# BV100011_ControlDI_8-15.net
KiCad netlist of a schematic drawn in Altium Designer
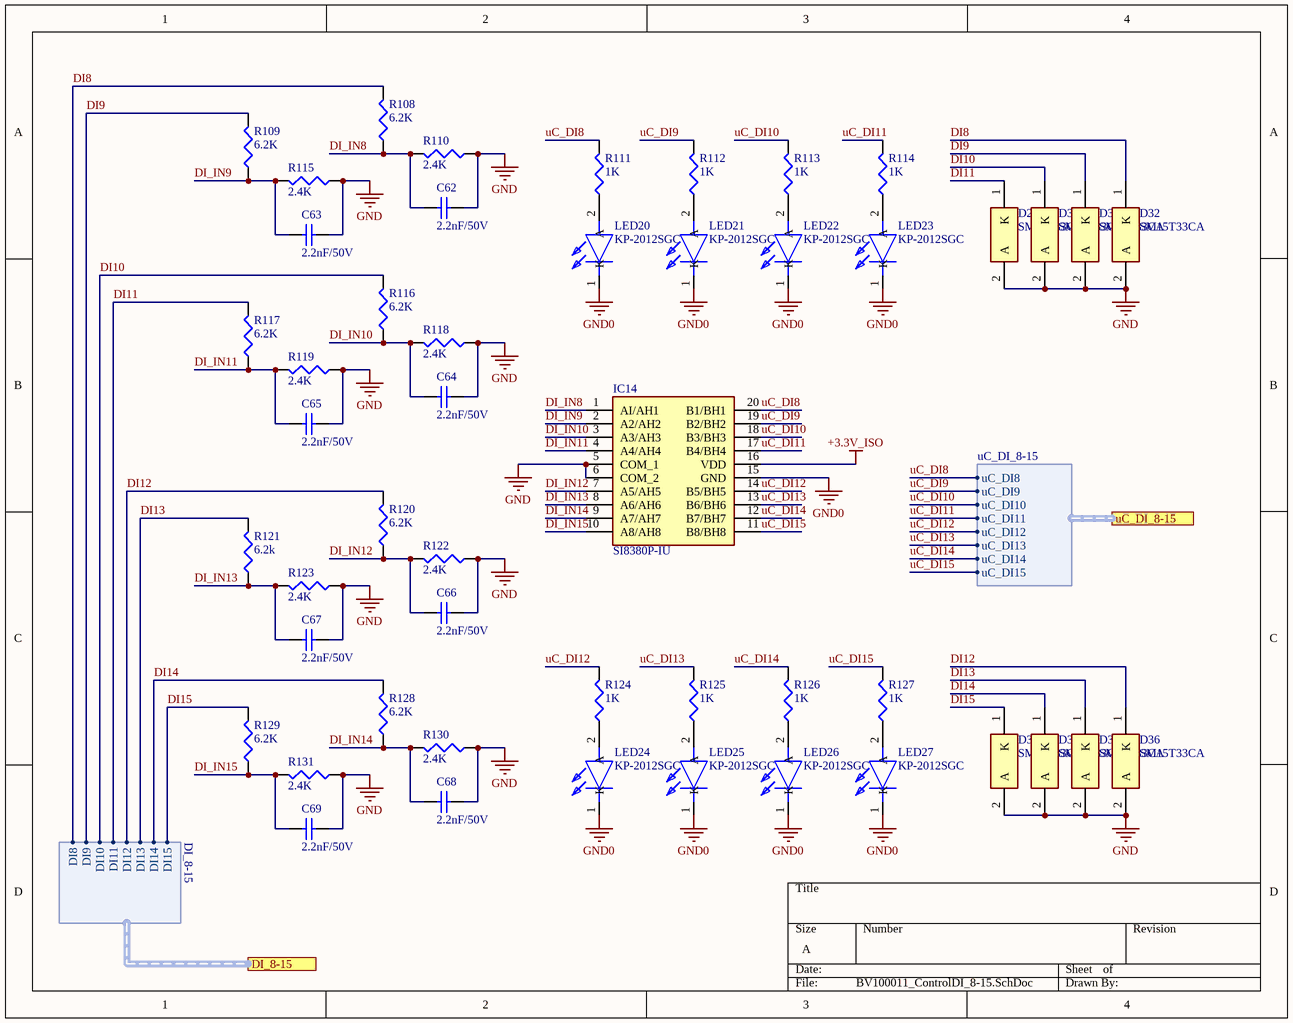
[diagram p0: BV100011_ControlDI_8-15.SchDoc]

(export (version "E")
  (design (tool "Eeschema 10.0.6"))
  (components
    (comp (ref "C62")
      (value "2.2nF/50V")
      (footprint "C1210")
      (description "Capacitor (Semiconductor SIM Model)")
      (fields (field (name "PUBLISHER") "Altium Limited"))
      (libsource (lib "Miscellaneous Devices") (part "Cap Semi"))
    )
    (comp (ref "C63")
      (value "2.2nF/50V")
      (footprint "C1210")
      (description "Capacitor (Semiconductor SIM Model)")
      (fields (field (name "PUBLISHER") "Altium Limited"))
      (libsource (lib "Miscellaneous Devices") (part "Cap Semi"))
    )
    (comp (ref "C64")
      (value "2.2nF/50V")
      (footprint "C1210")
      (description "Capacitor (Semiconductor SIM Model)")
      (fields (field (name "PUBLISHER") "Altium Limited"))
      (libsource (lib "Miscellaneous Devices") (part "Cap Semi"))
    )
    (comp (ref "C65")
      (value "2.2nF/50V")
      (footprint "C1210")
      (description "Capacitor (Semiconductor SIM Model)")
      (fields (field (name "PUBLISHER") "Altium Limited"))
      (libsource (lib "Miscellaneous Devices") (part "Cap Semi"))
    )
    (comp (ref "C66")
      (value "2.2nF/50V")
      (footprint "C1210")
      (description "Capacitor (Semiconductor SIM Model)")
      (fields (field (name "PUBLISHER") "Altium Limited"))
      (libsource (lib "Miscellaneous Devices") (part "Cap Semi"))
    )
    (comp (ref "C67")
      (value "2.2nF/50V")
      (footprint "C1210")
      (description "Capacitor (Semiconductor SIM Model)")
      (fields (field (name "PUBLISHER") "Altium Limited"))
      (libsource (lib "Miscellaneous Devices") (part "Cap Semi"))
    )
    (comp (ref "C68")
      (value "2.2nF/50V")
      (footprint "C1210")
      (description "Capacitor (Semiconductor SIM Model)")
      (fields (field (name "PUBLISHER") "Altium Limited"))
      (libsource (lib "Miscellaneous Devices") (part "Cap Semi"))
    )
    (comp (ref "C69")
      (value "2.2nF/50V")
      (footprint "C1210")
      (description "Capacitor (Semiconductor SIM Model)")
      (fields (field (name "PUBLISHER") "Altium Limited"))
      (libsource (lib "Miscellaneous Devices") (part "Cap Semi"))
    )
    (comp (ref "D29")
      (value "SM15T33CA")
      (footprint "DIONM8059X265N")
      (description "Diode")
      (fields (field (name "MOUSER PART NUMBER") "511-SM15T33CA") (field (name "RS PART NUMBER") "9196428"))
      (libsource (lib "SM15T33CA") (part "SM15T33CA"))
    )
    (comp (ref "D30")
      (value "SM15T33CA")
      (footprint "DIONM8059X265N")
      (description "Diode")
      (fields (field (name "MOUSER PART NUMBER") "511-SM15T33CA") (field (name "RS PART NUMBER") "9196428"))
      (libsource (lib "SM15T33CA") (part "SM15T33CA"))
    )
    (comp (ref "D31")
      (value "SM15T33CA")
      (footprint "DIONM8059X265N")
      (description "Diode")
      (fields (field (name "MOUSER PART NUMBER") "511-SM15T33CA") (field (name "RS PART NUMBER") "9196428"))
      (libsource (lib "SM15T33CA") (part "SM15T33CA"))
    )
    (comp (ref "D32")
      (value "SM15T33CA")
      (footprint "DIONM8059X265N")
      (description "Diode")
      (fields (field (name "MOUSER PART NUMBER") "511-SM15T33CA") (field (name "RS PART NUMBER") "9196428"))
      (libsource (lib "SM15T33CA") (part "SM15T33CA"))
    )
    (comp (ref "D33")
      (value "SM15T33CA")
      (footprint "DIONM8059X265N")
      (description "Diode")
      (fields (field (name "MOUSER PART NUMBER") "511-SM15T33CA") (field (name "RS PART NUMBER") "9196428"))
      (libsource (lib "SM15T33CA") (part "SM15T33CA"))
    )
    (comp (ref "D34")
      (value "SM15T33CA")
      (footprint "DIONM8059X265N")
      (description "Diode")
      (fields (field (name "MOUSER PART NUMBER") "511-SM15T33CA") (field (name "RS PART NUMBER") "9196428"))
      (libsource (lib "SM15T33CA") (part "SM15T33CA"))
    )
    (comp (ref "D35")
      (value "SM15T33CA")
      (footprint "DIONM8059X265N")
      (description "Diode")
      (fields (field (name "MOUSER PART NUMBER") "511-SM15T33CA") (field (name "RS PART NUMBER") "9196428"))
      (libsource (lib "SM15T33CA") (part "SM15T33CA"))
    )
    (comp (ref "D36")
      (value "SM15T33CA")
      (footprint "DIONM8059X265N")
      (description "Diode")
      (fields (field (name "MOUSER PART NUMBER") "511-SM15T33CA") (field (name "RS PART NUMBER") "9196428"))
      (libsource (lib "SM15T33CA") (part "SM15T33CA"))
    )
    (comp (ref "IC14")
      (value "SI8380P-IU")
      (footprint "SOP64P600X175-20N")
      (description "Integrated Circuit")
      (fields (field (name "MOUSER PART NUMBER") "634-SI8380P-IU"))
      (libsource (lib "SI8380P-IU") (part "SI8380P-IU"))
    )
    (comp (ref "LED20")
      (value "KP-2012SGC")
      (footprint "LEDC2012X110N")
      (description "LED")
      (fields (field (name "RS PART NUMBER") "4663807"))
      (libsource (lib "POWER_LED") (part "KP-2012SGC"))
    )
    (comp (ref "LED21")
      (value "KP-2012SGC")
      (footprint "LEDC2012X110N")
      (description "LED")
      (fields (field (name "RS PART NUMBER") "4663807"))
      (libsource (lib "POWER_LED") (part "KP-2012SGC"))
    )
    (comp (ref "LED22")
      (value "KP-2012SGC")
      (footprint "LEDC2012X110N")
      (description "LED")
      (fields (field (name "RS PART NUMBER") "4663807"))
      (libsource (lib "POWER_LED") (part "KP-2012SGC"))
    )
    (comp (ref "LED23")
      (value "KP-2012SGC")
      (footprint "LEDC2012X110N")
      (description "LED")
      (fields (field (name "RS PART NUMBER") "4663807"))
      (libsource (lib "POWER_LED") (part "KP-2012SGC"))
    )
    (comp (ref "LED24")
      (value "KP-2012SGC")
      (footprint "LEDC2012X110N")
      (description "LED")
      (fields (field (name "RS PART NUMBER") "4663807"))
      (libsource (lib "POWER_LED") (part "KP-2012SGC"))
    )
    (comp (ref "LED25")
      (value "KP-2012SGC")
      (footprint "LEDC2012X110N")
      (description "LED")
      (fields (field (name "RS PART NUMBER") "4663807"))
      (libsource (lib "POWER_LED") (part "KP-2012SGC"))
    )
    (comp (ref "LED26")
      (value "KP-2012SGC")
      (footprint "LEDC2012X110N")
      (description "LED")
      (fields (field (name "RS PART NUMBER") "4663807"))
      (libsource (lib "POWER_LED") (part "KP-2012SGC"))
    )
    (comp (ref "LED27")
      (value "KP-2012SGC")
      (footprint "LEDC2012X110N")
      (description "LED")
      (fields (field (name "RS PART NUMBER") "4663807"))
      (libsource (lib "POWER_LED") (part "KP-2012SGC"))
    )
    (comp (ref "R108")
      (value "6.2K")
      (footprint "12Z-2010")
      (description "Resistor")
      (fields (field (name "PUBLISHER") "Altium Limited"))
      (libsource (lib "Miscellaneous Devices") (part "Res3"))
    )
    (comp (ref "R109")
      (value "6.2K")
      (footprint "12Z-2010")
      (description "Resistor")
      (fields (field (name "PUBLISHER") "Altium Limited"))
      (libsource (lib "Miscellaneous Devices") (part "Res3"))
    )
    (comp (ref "R110")
      (value "2.4K")
      (footprint "12Z-2010")
      (description "Resistor")
      (fields (field (name "PUBLISHER") "Altium Limited"))
      (libsource (lib "Miscellaneous Devices") (part "Res3"))
    )
    (comp (ref "R111")
      (value "1K")
      (footprint "0402")
      (description "Resistor")
      (fields (field (name "PUBLISHER") "Altium Limited"))
      (libsource (lib "Miscellaneous Devices") (part "Res3"))
    )
    (comp (ref "R112")
      (value "1K")
      (footprint "0402")
      (description "Resistor")
      (fields (field (name "PUBLISHER") "Altium Limited"))
      (libsource (lib "Miscellaneous Devices") (part "Res3"))
    )
    (comp (ref "R113")
      (value "1K")
      (footprint "0402")
      (description "Resistor")
      (fields (field (name "PUBLISHER") "Altium Limited"))
      (libsource (lib "Miscellaneous Devices") (part "Res3"))
    )
    (comp (ref "R114")
      (value "1K")
      (footprint "0402")
      (description "Resistor")
      (fields (field (name "PUBLISHER") "Altium Limited"))
      (libsource (lib "Miscellaneous Devices") (part "Res3"))
    )
    (comp (ref "R115")
      (value "2.4K")
      (footprint "12Z-2010")
      (description "Resistor")
      (fields (field (name "PUBLISHER") "Altium Limited"))
      (libsource (lib "Miscellaneous Devices") (part "Res3"))
    )
    (comp (ref "R116")
      (value "6.2K")
      (footprint "12Z-2010")
      (description "Resistor")
      (fields (field (name "PUBLISHER") "Altium Limited"))
      (libsource (lib "Miscellaneous Devices") (part "Res3"))
    )
    (comp (ref "R117")
      (value "6.2K")
      (footprint "12Z-2010")
      (description "Resistor")
      (fields (field (name "PUBLISHER") "Altium Limited"))
      (libsource (lib "Miscellaneous Devices") (part "Res3"))
    )
    (comp (ref "R118")
      (value "2.4K")
      (footprint "12Z-2010")
      (description "Resistor")
      (fields (field (name "PUBLISHER") "Altium Limited"))
      (libsource (lib "Miscellaneous Devices") (part "Res3"))
    )
    (comp (ref "R119")
      (value "2.4K")
      (footprint "12Z-2010")
      (description "Resistor")
      (fields (field (name "PUBLISHER") "Altium Limited"))
      (libsource (lib "Miscellaneous Devices") (part "Res3"))
    )
    (comp (ref "R120")
      (value "6.2K")
      (footprint "12Z-2010")
      (description "Resistor")
      (fields (field (name "PUBLISHER") "Altium Limited"))
      (libsource (lib "Miscellaneous Devices") (part "Res3"))
    )
    (comp (ref "R121")
      (value "6.2k")
      (footprint "12Z-2010")
      (description "Resistor")
      (fields (field (name "PUBLISHER") "Altium Limited"))
      (libsource (lib "Miscellaneous Devices") (part "Res3"))
    )
    (comp (ref "R122")
      (value "2.4K")
      (footprint "12Z-2010")
      (description "Resistor")
      (fields (field (name "PUBLISHER") "Altium Limited"))
      (libsource (lib "Miscellaneous Devices") (part "Res3"))
    )
    (comp (ref "R123")
      (value "2.4K")
      (footprint "12Z-2010")
      (description "Resistor")
      (fields (field (name "PUBLISHER") "Altium Limited"))
      (libsource (lib "Miscellaneous Devices") (part "Res3"))
    )
    (comp (ref "R124")
      (value "1K")
      (footprint "0402")
      (description "Resistor")
      (fields (field (name "PUBLISHER") "Altium Limited"))
      (libsource (lib "Miscellaneous Devices") (part "Res3"))
    )
    (comp (ref "R125")
      (value "1K")
      (footprint "0402")
      (description "Resistor")
      (fields (field (name "PUBLISHER") "Altium Limited"))
      (libsource (lib "Miscellaneous Devices") (part "Res3"))
    )
    (comp (ref "R126")
      (value "1K")
      (footprint "0402")
      (description "Resistor")
      (fields (field (name "PUBLISHER") "Altium Limited"))
      (libsource (lib "Miscellaneous Devices") (part "Res3"))
    )
    (comp (ref "R127")
      (value "1K")
      (footprint "0402")
      (description "Resistor")
      (fields (field (name "PUBLISHER") "Altium Limited"))
      (libsource (lib "Miscellaneous Devices") (part "Res3"))
    )
    (comp (ref "R128")
      (value "6.2K")
      (footprint "12Z-2010")
      (description "Resistor")
      (fields (field (name "PUBLISHER") "Altium Limited"))
      (libsource (lib "Miscellaneous Devices") (part "Res3"))
    )
    (comp (ref "R129")
      (value "6.2K")
      (footprint "12Z-2010")
      (description "Resistor")
      (fields (field (name "PUBLISHER") "Altium Limited"))
      (libsource (lib "Miscellaneous Devices") (part "Res3"))
    )
    (comp (ref "R130")
      (value "2.4K")
      (footprint "12Z-2010")
      (description "Resistor")
      (fields (field (name "PUBLISHER") "Altium Limited"))
      (libsource (lib "Miscellaneous Devices") (part "Res3"))
    )
    (comp (ref "R131")
      (value "2.4K")
      (footprint "12Z-2010")
      (description "Resistor")
      (fields (field (name "PUBLISHER") "Altium Limited"))
      (libsource (lib "Miscellaneous Devices") (part "Res3"))
    )
  )
  (nets
    (net (code "3") (name "+3.3V_ISO") (class "Default")
      (node (ref "IC14") (pin "16") (pinfunction "VDD_16") (pintype "passive"))
    )
    (net (code "4") (name "/DI8") (class "Default")
      (node (ref "D32") (pin "1") (pinfunction "K_1") (pintype "passive"))
      (node (ref "R108") (pin "2") (pinfunction "2_2") (pintype "passive"))
    )
    (net (code "5") (name "/DI9") (class "Default")
      (node (ref "D31") (pin "1") (pinfunction "K_1") (pintype "passive"))
      (node (ref "R109") (pin "2") (pinfunction "2_2") (pintype "passive"))
    )
    (net (code "6") (name "/DI10") (class "Default")
      (node (ref "D30") (pin "1") (pinfunction "K_1") (pintype "passive"))
      (node (ref "R116") (pin "2") (pinfunction "2_2") (pintype "passive"))
    )
    (net (code "7") (name "/DI11") (class "Default")
      (node (ref "D29") (pin "1") (pinfunction "K_1") (pintype "passive"))
      (node (ref "R117") (pin "2") (pinfunction "2_2") (pintype "passive"))
    )
    (net (code "8") (name "/DI12") (class "Default")
      (node (ref "D36") (pin "1") (pinfunction "K_1") (pintype "passive"))
      (node (ref "R120") (pin "2") (pinfunction "2_2") (pintype "passive"))
    )
    (net (code "9") (name "/DI13") (class "Default")
      (node (ref "D35") (pin "1") (pinfunction "K_1") (pintype "passive"))
      (node (ref "R121") (pin "2") (pinfunction "2_2") (pintype "passive"))
    )
    (net (code "10") (name "/DI14") (class "Default")
      (node (ref "D34") (pin "1") (pinfunction "K_1") (pintype "passive"))
      (node (ref "R128") (pin "2") (pinfunction "2_2") (pintype "passive"))
    )
    (net (code "11") (name "/DI15") (class "Default")
      (node (ref "D33") (pin "1") (pinfunction "K_1") (pintype "passive"))
      (node (ref "R129") (pin "2") (pinfunction "2_2") (pintype "passive"))
    )
    (net (code "12") (name "/DI_IN8") (class "Default")
      (node (ref "C62") (pin "1") (pinfunction "1_1") (pintype "passive"))
      (node (ref "IC14") (pin "1") (pinfunction "AI/AH1_1") (pintype "passive"))
      (node (ref "R108") (pin "1") (pinfunction "1_1") (pintype "passive"))
      (node (ref "R110") (pin "2") (pinfunction "2_2") (pintype "passive"))
    )
    (net (code "13") (name "/DI_IN9") (class "Default")
      (node (ref "C63") (pin "1") (pinfunction "1_1") (pintype "passive"))
      (node (ref "IC14") (pin "2") (pinfunction "A2/AH2_2") (pintype "passive"))
      (node (ref "R109") (pin "1") (pinfunction "1_1") (pintype "passive"))
      (node (ref "R115") (pin "2") (pinfunction "2_2") (pintype "passive"))
    )
    (net (code "14") (name "/DI_IN10") (class "Default")
      (node (ref "C64") (pin "1") (pinfunction "1_1") (pintype "passive"))
      (node (ref "IC14") (pin "3") (pinfunction "A3/AH3_3") (pintype "passive"))
      (node (ref "R116") (pin "1") (pinfunction "1_1") (pintype "passive"))
      (node (ref "R118") (pin "2") (pinfunction "2_2") (pintype "passive"))
    )
    (net (code "15") (name "/DI_IN11") (class "Default")
      (node (ref "C65") (pin "1") (pinfunction "1_1") (pintype "passive"))
      (node (ref "IC14") (pin "4") (pinfunction "A4/AH4_4") (pintype "passive"))
      (node (ref "R117") (pin "1") (pinfunction "1_1") (pintype "passive"))
      (node (ref "R119") (pin "2") (pinfunction "2_2") (pintype "passive"))
    )
    (net (code "16") (name "/DI_IN12") (class "Default")
      (node (ref "C66") (pin "1") (pinfunction "1_1") (pintype "passive"))
      (node (ref "IC14") (pin "7") (pinfunction "A5/AH5_7") (pintype "passive"))
      (node (ref "R120") (pin "1") (pinfunction "1_1") (pintype "passive"))
      (node (ref "R122") (pin "2") (pinfunction "2_2") (pintype "passive"))
    )
    (net (code "17") (name "/DI_IN13") (class "Default")
      (node (ref "C67") (pin "1") (pinfunction "1_1") (pintype "passive"))
      (node (ref "IC14") (pin "8") (pinfunction "A6/AH6_8") (pintype "passive"))
      (node (ref "R121") (pin "1") (pinfunction "1_1") (pintype "passive"))
      (node (ref "R123") (pin "2") (pinfunction "2_2") (pintype "passive"))
    )
    (net (code "18") (name "/DI_IN14") (class "Default")
      (node (ref "C68") (pin "1") (pinfunction "1_1") (pintype "passive"))
      (node (ref "IC14") (pin "9") (pinfunction "A7/AH7_9") (pintype "passive"))
      (node (ref "R128") (pin "1") (pinfunction "1_1") (pintype "passive"))
      (node (ref "R130") (pin "2") (pinfunction "2_2") (pintype "passive"))
    )
    (net (code "19") (name "/DI_IN15") (class "Default")
      (node (ref "C69") (pin "1") (pinfunction "1_1") (pintype "passive"))
      (node (ref "IC14") (pin "10") (pinfunction "A8/AH8_10") (pintype "passive"))
      (node (ref "R129") (pin "1") (pinfunction "1_1") (pintype "passive"))
      (node (ref "R131") (pin "2") (pinfunction "2_2") (pintype "passive"))
    )
    (net (code "20") (name "/uC_DI8") (class "Default")
      (node (ref "IC14") (pin "20") (pinfunction "B1/BH1_20") (pintype "passive"))
      (node (ref "R111") (pin "2") (pinfunction "2_2") (pintype "passive"))
    )
    (net (code "21") (name "/uC_DI9") (class "Default")
      (node (ref "IC14") (pin "19") (pinfunction "B2/BH2_19") (pintype "passive"))
      (node (ref "R112") (pin "2") (pinfunction "2_2") (pintype "passive"))
    )
    (net (code "22") (name "/uC_DI10") (class "Default")
      (node (ref "IC14") (pin "18") (pinfunction "B3/BH3_18") (pintype "passive"))
      (node (ref "R113") (pin "2") (pinfunction "2_2") (pintype "passive"))
    )
    (net (code "23") (name "/uC_DI11") (class "Default")
      (node (ref "IC14") (pin "17") (pinfunction "B4/BH4_17") (pintype "passive"))
      (node (ref "R114") (pin "2") (pinfunction "2_2") (pintype "passive"))
    )
    (net (code "24") (name "/uC_DI12") (class "Default")
      (node (ref "IC14") (pin "14") (pinfunction "B5/BH5_14") (pintype "passive"))
      (node (ref "R124") (pin "2") (pinfunction "2_2") (pintype "passive"))
    )
    (net (code "25") (name "/uC_DI13") (class "Default")
      (node (ref "IC14") (pin "13") (pinfunction "B6/BH6_13") (pintype "passive"))
      (node (ref "R125") (pin "2") (pinfunction "2_2") (pintype "passive"))
    )
    (net (code "26") (name "/uC_DI14") (class "Default")
      (node (ref "IC14") (pin "12") (pinfunction "B7/BH7_12") (pintype "passive"))
      (node (ref "R126") (pin "2") (pinfunction "2_2") (pintype "passive"))
    )
    (net (code "27") (name "/uC_DI15") (class "Default")
      (node (ref "IC14") (pin "11") (pinfunction "B8/BH8_11") (pintype "passive"))
      (node (ref "R127") (pin "2") (pinfunction "2_2") (pintype "passive"))
    )
    (net (code "30") (name "GND") (class "Default")
      (node (ref "C62") (pin "2") (pinfunction "2_2") (pintype "passive"))
      (node (ref "C63") (pin "2") (pinfunction "2_2") (pintype "passive"))
      (node (ref "C64") (pin "2") (pinfunction "2_2") (pintype "passive"))
      (node (ref "C65") (pin "2") (pinfunction "2_2") (pintype "passive"))
      (node (ref "C66") (pin "2") (pinfunction "2_2") (pintype "passive"))
      (node (ref "C67") (pin "2") (pinfunction "2_2") (pintype "passive"))
      (node (ref "C68") (pin "2") (pinfunction "2_2") (pintype "passive"))
      (node (ref "C69") (pin "2") (pinfunction "2_2") (pintype "passive"))
      (node (ref "D29") (pin "2") (pinfunction "A_2") (pintype "passive"))
      (node (ref "D30") (pin "2") (pinfunction "A_2") (pintype "passive"))
      (node (ref "D31") (pin "2") (pinfunction "A_2") (pintype "passive"))
      (node (ref "D32") (pin "2") (pinfunction "A_2") (pintype "passive"))
      (node (ref "D33") (pin "2") (pinfunction "A_2") (pintype "passive"))
      (node (ref "D34") (pin "2") (pinfunction "A_2") (pintype "passive"))
      (node (ref "D35") (pin "2") (pinfunction "A_2") (pintype "passive"))
      (node (ref "D36") (pin "2") (pinfunction "A_2") (pintype "passive"))
      (node (ref "IC14") (pin "5") (pinfunction "COM_1_5") (pintype "passive"))
      (node (ref "IC14") (pin "6") (pinfunction "COM_2_6") (pintype "passive"))
      (node (ref "R110") (pin "1") (pinfunction "1_1") (pintype "passive"))
      (node (ref "R115") (pin "1") (pinfunction "1_1") (pintype "passive"))
      (node (ref "R118") (pin "1") (pinfunction "1_1") (pintype "passive"))
      (node (ref "R119") (pin "1") (pinfunction "1_1") (pintype "passive"))
      (node (ref "R122") (pin "1") (pinfunction "1_1") (pintype "passive"))
      (node (ref "R123") (pin "1") (pinfunction "1_1") (pintype "passive"))
      (node (ref "R130") (pin "1") (pinfunction "1_1") (pintype "passive"))
      (node (ref "R131") (pin "1") (pinfunction "1_1") (pintype "passive"))
    )
    (net (code "31") (name "GND0") (class "Default")
      (node (ref "IC14") (pin "15") (pinfunction "GND_15") (pintype "passive"))
      (node (ref "LED20") (pin "1") (pinfunction "K_1") (pintype "passive"))
      (node (ref "LED21") (pin "1") (pinfunction "K_1") (pintype "passive"))
      (node (ref "LED22") (pin "1") (pinfunction "K_1") (pintype "passive"))
      (node (ref "LED23") (pin "1") (pinfunction "K_1") (pintype "passive"))
      (node (ref "LED24") (pin "1") (pinfunction "K_1") (pintype "passive"))
      (node (ref "LED25") (pin "1") (pinfunction "K_1") (pintype "passive"))
      (node (ref "LED26") (pin "1") (pinfunction "K_1") (pintype "passive"))
      (node (ref "LED27") (pin "1") (pinfunction "K_1") (pintype "passive"))
    )
    (net (code "32") (name "Net-(LED20-A)") (class "Default")
      (node (ref "LED20") (pin "2") (pinfunction "A_2") (pintype "passive"))
      (node (ref "R111") (pin "1") (pinfunction "1_1") (pintype "passive"))
    )
    (net (code "33") (name "Net-(LED21-A)") (class "Default")
      (node (ref "LED21") (pin "2") (pinfunction "A_2") (pintype "passive"))
      (node (ref "R112") (pin "1") (pinfunction "1_1") (pintype "passive"))
    )
    (net (code "34") (name "Net-(LED22-A)") (class "Default")
      (node (ref "LED22") (pin "2") (pinfunction "A_2") (pintype "passive"))
      (node (ref "R113") (pin "1") (pinfunction "1_1") (pintype "passive"))
    )
    (net (code "35") (name "Net-(LED23-A)") (class "Default")
      (node (ref "LED23") (pin "2") (pinfunction "A_2") (pintype "passive"))
      (node (ref "R114") (pin "1") (pinfunction "1_1") (pintype "passive"))
    )
    (net (code "36") (name "Net-(LED24-A)") (class "Default")
      (node (ref "LED24") (pin "2") (pinfunction "A_2") (pintype "passive"))
      (node (ref "R124") (pin "1") (pinfunction "1_1") (pintype "passive"))
    )
    (net (code "37") (name "Net-(LED25-A)") (class "Default")
      (node (ref "LED25") (pin "2") (pinfunction "A_2") (pintype "passive"))
      (node (ref "R125") (pin "1") (pinfunction "1_1") (pintype "passive"))
    )
    (net (code "38") (name "Net-(LED26-A)") (class "Default")
      (node (ref "LED26") (pin "2") (pinfunction "A_2") (pintype "passive"))
      (node (ref "R126") (pin "1") (pinfunction "1_1") (pintype "passive"))
    )
    (net (code "39") (name "Net-(LED27-A)") (class "Default")
      (node (ref "LED27") (pin "2") (pinfunction "A_2") (pintype "passive"))
      (node (ref "R127") (pin "1") (pinfunction "1_1") (pintype "passive"))
    )
  )
)
